# H21R2.net
KiCad netlist of a schematic drawn in EAGLE
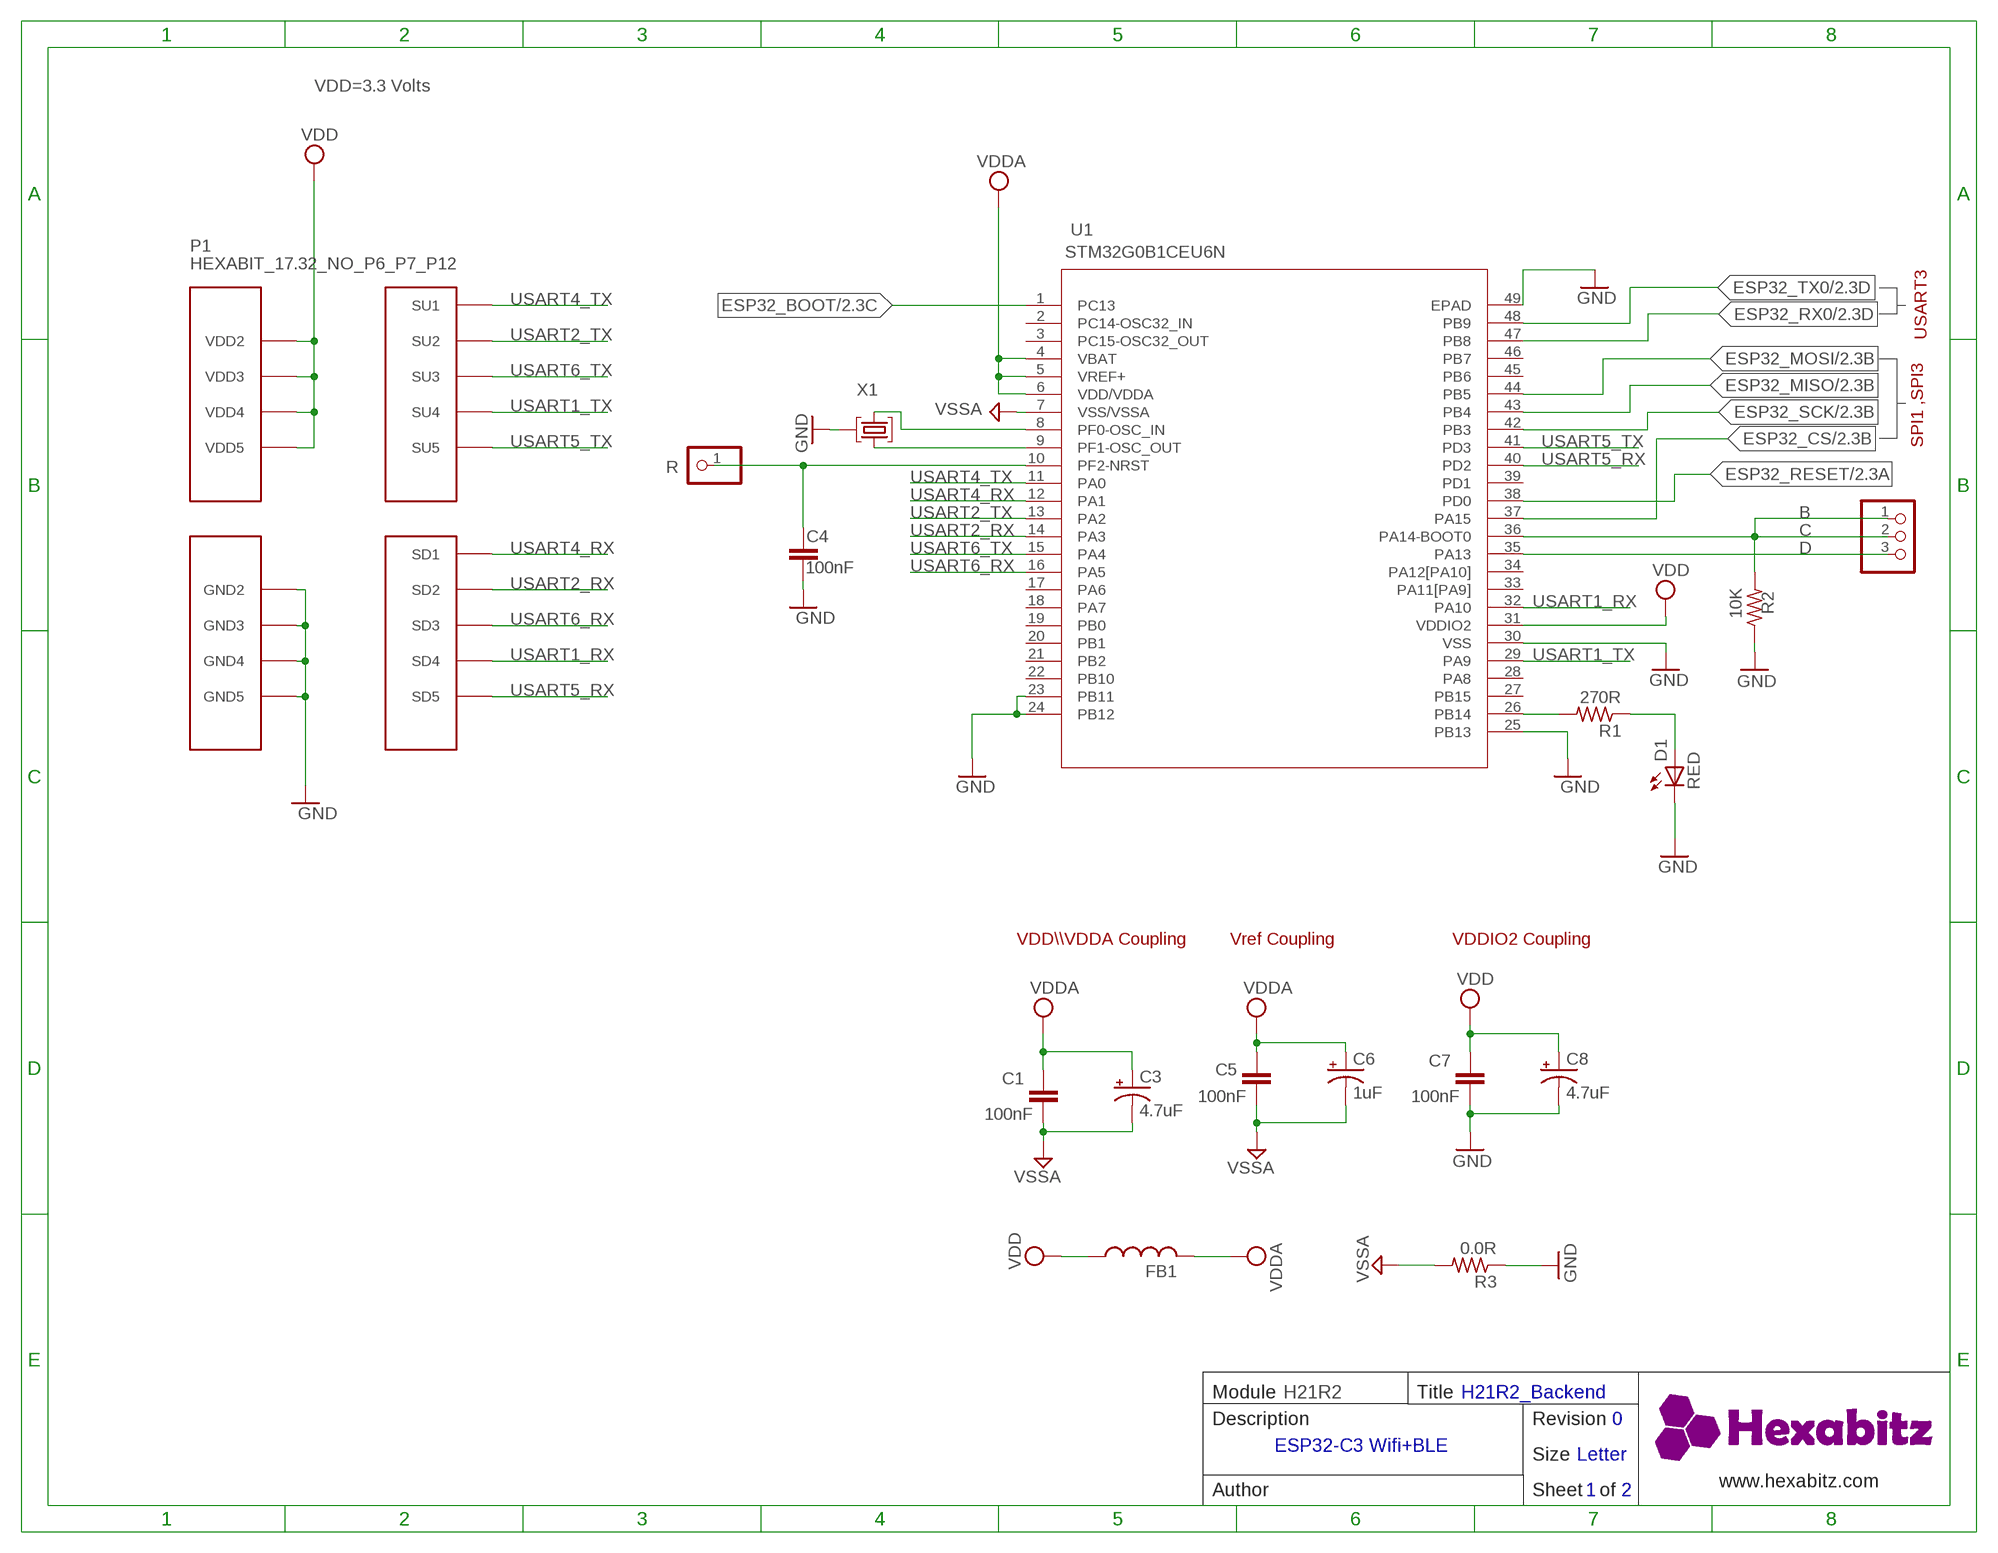
[diagram p0: schematic, sheet 1]
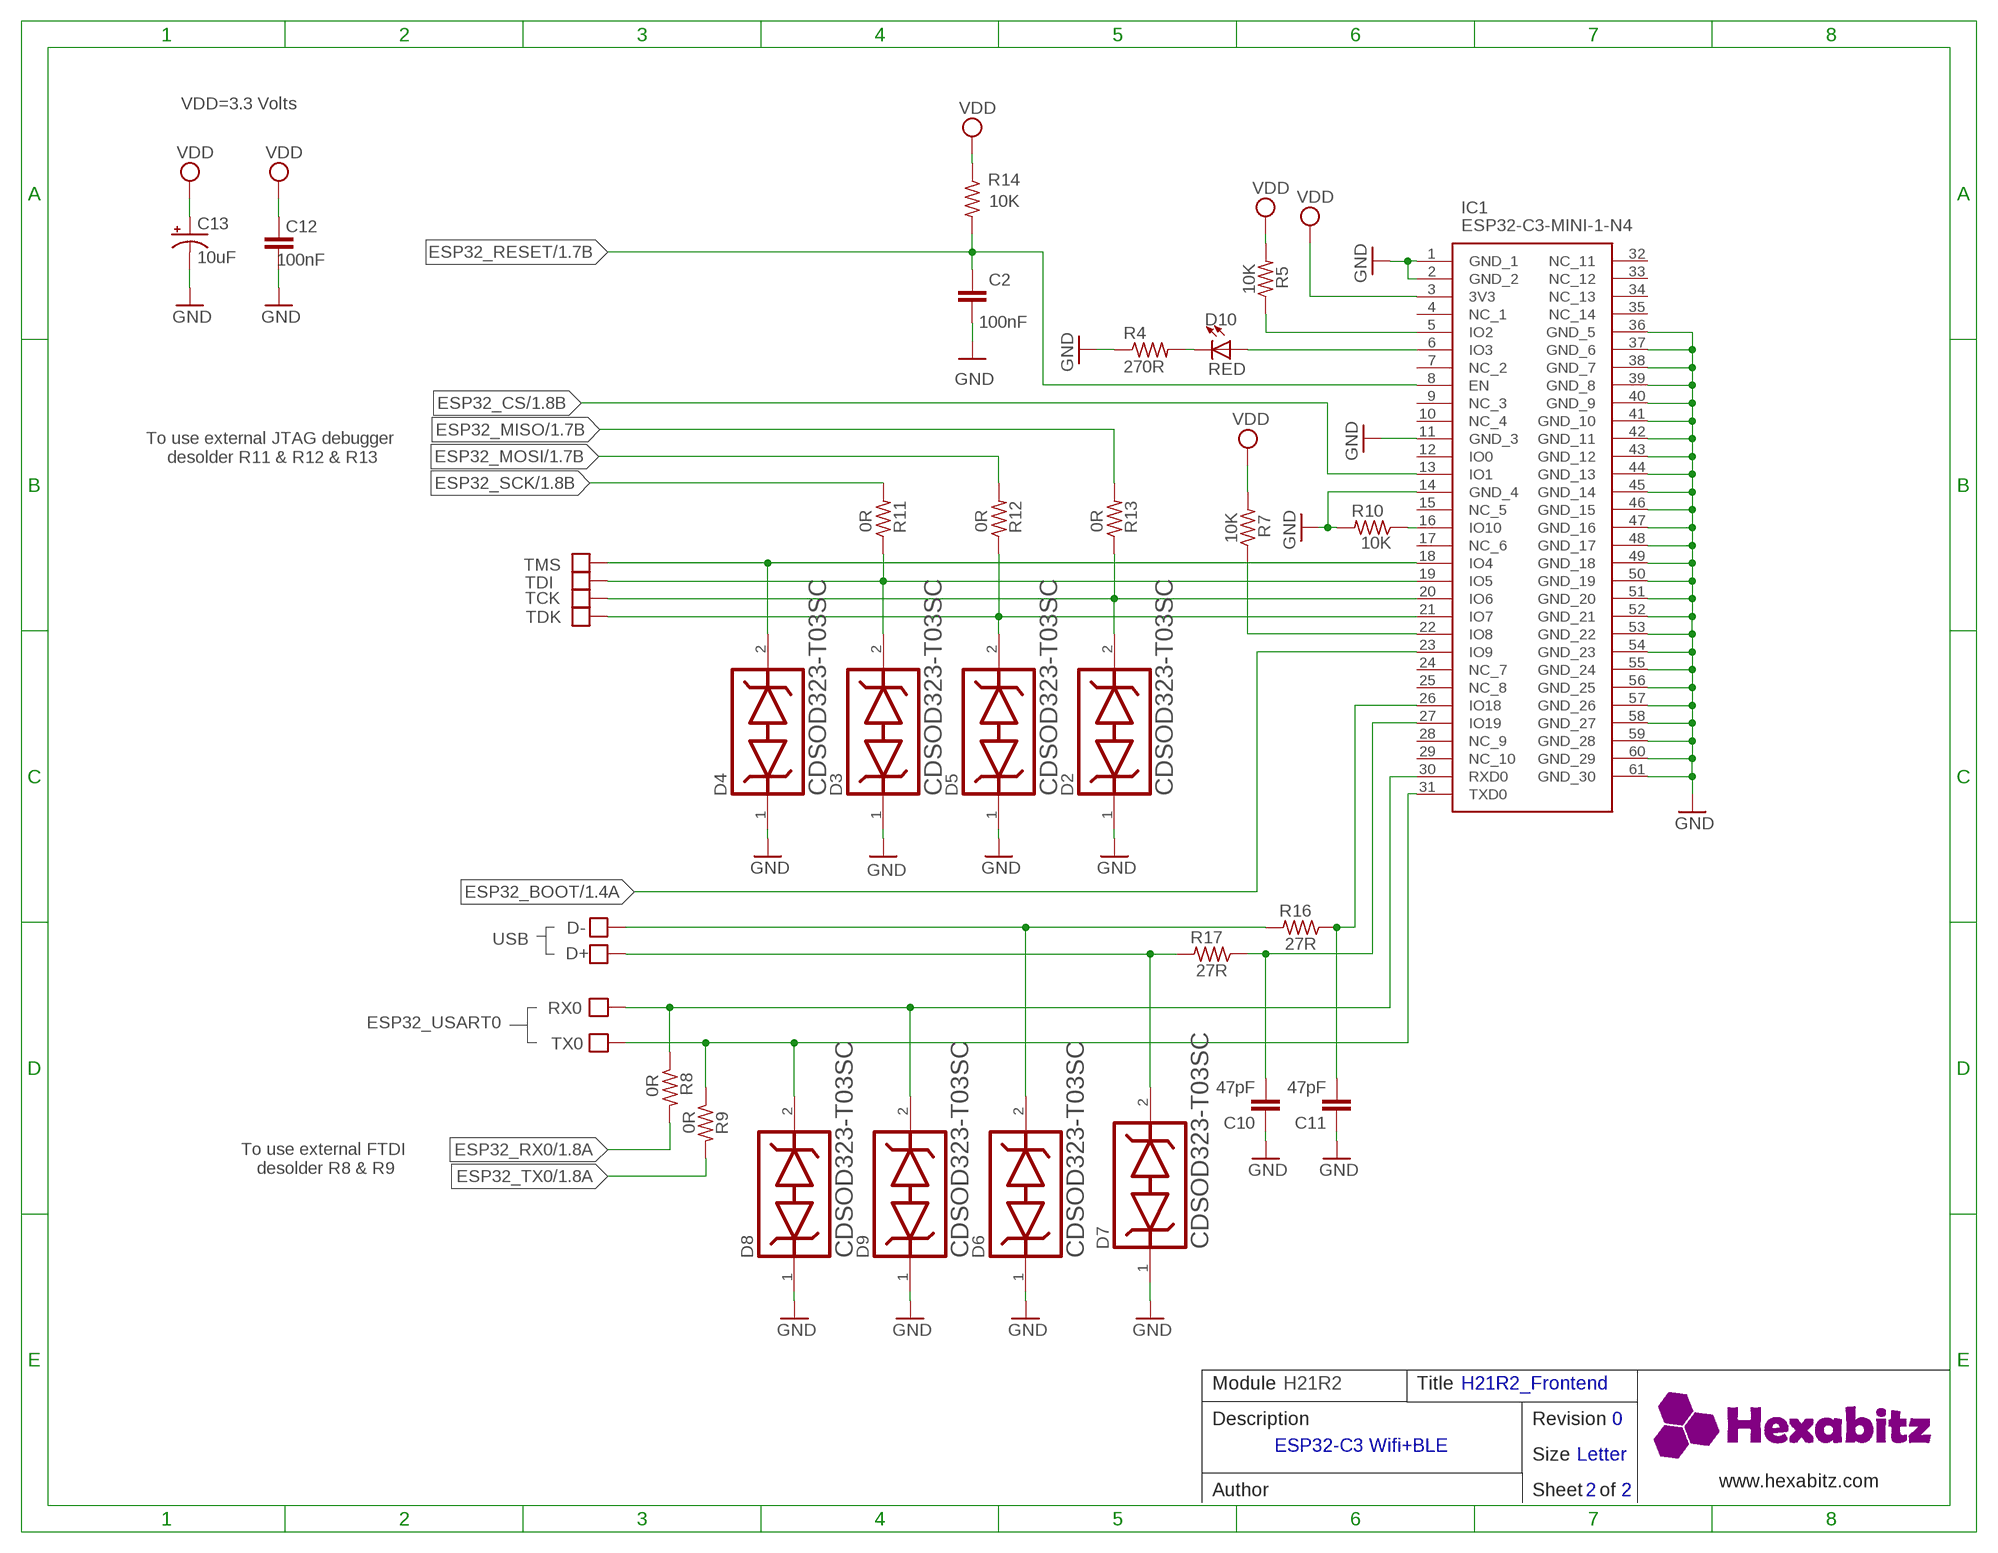
[diagram p1: schematic, sheet 2]

(export (version "E")
  (design (tool "Eeschema 10.0.6"))
  (components
    (comp (ref "C1")
      (value "100nF")
      (footprint "eagle-import:C-0603")
      (fields
        (field (name "CAPACITANCE") "100nF")
        (field (name "MFN") "AVX CORPORATION")
        (field (name "MPN") "'0603YC104K4T2A")
        (field (name "OCTOPART_URL") "'https://octopart.com/0603yc104k4t2a-avx+interconnect+%2F+elco-8120651")
        (field (name "TOLERANCE") "10%")
        (field (name "VOLTAGE_RATING") "16.0 V")
      )
      (libsource (lib "eagle-import") (part "C-0603"))
    )
    (comp (ref "C3")
      (value "4.7uF")
      (footprint "eagle-import:C-0805-POL")
      (fields
        (field (name "CAPACITANCE") "4.7uF")
        (field (name "MFN") "'Panasonic")
        (field (name "MPN") "'10TPU4R7MSI")
        (field (name "OCTOPART_URL") "https://octopart.com/10tpu4r7msi-panasonic-29487748?r=sp")
        (field (name "TOLERANCE") "20%")
        (field (name "VOLTAGE_RATING") "10.0 V")
      )
      (libsource (lib "eagle-import") (part "C-0805-POL"))
    )
    (comp (ref "C4")
      (value "100nF")
      (footprint "eagle-import:C-0603")
      (fields
        (field (name "CAPACITANCE") "100nF")
        (field (name "MFN") "AVX CORPORATION")
        (field (name "MPN") "0603YC104K4T2A")
        (field (name "OCTOPART_URL") "'https://octopart.com/0603yc104k4t2a-avx+interconnect+%2F+elco-8120651")
        (field (name "TOLERANCE") "10%")
        (field (name "VOLTAGE_RATING") "16.0 V")
      )
      (libsource (lib "eagle-import") (part "C-0603"))
    )
    (comp (ref "C5")
      (value "100nF")
      (footprint "eagle-import:C-0603")
      (fields
        (field (name "CAPACITANCE") "100nF")
        (field (name "MFN") "AVX CORPORATION")
        (field (name "MPN") "'0603YC104K4T2A")
        (field (name "OCTOPART_URL") "'https://octopart.com/0603yc104k4t2a-avx+interconnect+%2F+elco-8120651")
        (field (name "TOLERANCE") "10%")
        (field (name "VOLTAGE_RATING") "16.0 V")
      )
      (libsource (lib "eagle-import") (part "C-0603"))
    )
    (comp (ref "C6")
      (value "1uF")
      (footprint "eagle-import:C-0805-POL")
      (fields
        (field (name "CAPACITANCE") "4.7uF")
        (field (name "MFN") "'YAGEO [VA]")
        (field (name "MPN") "'CC0805KKX7R7BB105")
        (field (name "OCTOPART_URL") "'https://octopart.com/cc0805kkx7r7bb105-yageo-8376555?r=sp")
        (field (name "TOLERANCE") "20%")
        (field (name "VOLTAGE_RATING") "10.0 V")
      )
      (libsource (lib "eagle-import") (part "C-0805-POL"))
    )
    (comp (ref "C7")
      (value "100nF")
      (footprint "eagle-import:C-0603")
      (fields
        (field (name "CAPACITANCE") "100nF")
        (field (name "MFN") "AVX CORPORATION")
        (field (name "MPN") "'0603YC104K4T2A")
        (field (name "OCTOPART_URL") "'https://octopart.com/0603yc104k4t2a-avx+interconnect+%2F+elco-8120651")
        (field (name "TOLERANCE") "10%")
        (field (name "VOLTAGE_RATING") "16.0 V")
      )
      (libsource (lib "eagle-import") (part "C-0603"))
    )
    (comp (ref "C8")
      (value "4.7uF")
      (footprint "eagle-import:C-0805-POL")
      (fields
        (field (name "CAPACITANCE") "1.00uF")
        (field (name "MFN") "'Panasonic")
        (field (name "MPN") "'10TPU4R7MSI")
        (field (name "OCTOPART_URL") "https://octopart.com/10tpu4r7msi-panasonic-29487748?r=sp")
        (field (name "TOLERANCE") "10%")
        (field (name "VOLTAGE_RATING") "16.0 V")
      )
      (libsource (lib "eagle-import") (part "C-0805-POL"))
    )
    (comp (ref "D1")
      (value "RED")
      (footprint "eagle-import:VLMS1300-GS08")
      (fields (field (name "MPN") "VLMS1300-GS08"))
      (libsource (lib "eagle-import") (part "VLMS1300-GS08"))
    )
    (comp (ref "FB1")
      (value "FB-TDK_MMZ1608Y300B")
      (footprint "eagle-import:FB-TDK_MMZ1608Y300B")
      (fields
        (field (name "MFN") "TDK ")
        (field (name "MPN") "MMZ1608Y300BTA00")
        (field (name "OCTOPART_URL") "https://octopart.com/mmz1608y300bta00-tdk-7906990?r=sp")
      )
      (libsource (lib "eagle-import") (part "FB-TDK_MMZ1608Y300B"))
    )
    (comp (ref "JP1")
      (value "PINHD-1X3")
      (footprint "eagle-import:1X03")
      (libsource (lib "eagle-import") (part "PINHD-1X3"))
    )
    (comp (ref "P1")
      (value "HEXABIT_17.32_NO_P6_P7_P12")
      (footprint "eagle-import:HEXABIT_17.32_NO_P6_P7_P12")
      (libsource (lib "eagle-import") (part "HEXABIT_?_NO_P6_P7_P1217.32"))
    )
    (comp (ref "R")
      (value "PINHD-1X1")
      (footprint "eagle-import:1X01")
      (fields (field (name "MPN") "87227-1"))
      (libsource (lib "eagle-import") (part "PINHD-1X1"))
    )
    (comp (ref "R1")
      (value "270R")
      (footprint "eagle-import:R-0603")
      (fields
        (field (name "MFN") "'Panasonic")
        (field (name "MPN") "'ERJ-3GEYJ271V")
        (field (name "OCTOPART_URL") "https://octopart.com/erj-3geyj271v-panasonic-55560546?r=sp")
        (field (name "RESISTANCE") "270R")
      )
      (libsource (lib "eagle-import") (part "R-0603"))
    )
    (comp (ref "R2")
      (value "10K")
      (footprint "eagle-import:R-0603")
      (fields
        (field (name "MFN") "Vishay")
        (field (name "MPN") "'060300J0103T5E")
        (field (name "OCTOPART_URL") "https://octopart.com/search?q=060300J0103T5E&currency=USD&specs=0")
        (field (name "RESISTANCE") "10K")
      )
      (libsource (lib "eagle-import") (part "R-0603"))
    )
    (comp (ref "R3")
      (value "0.0R")
      (footprint "eagle-import:R-0603")
      (fields
        (field (name "MFN") "YAGEO [VR]")
        (field (name "MPN") "RC0603JR-070RL")
        (field (name "OCTOPART_URL") "https://octopart.com/rc0603jr-070rl-yageo-1241539?r=sp")
        (field (name "RESISTANCE") "0R")
      )
      (libsource (lib "eagle-import") (part "R-0603"))
    )
    (comp (ref "U1")
      (value "STM32G0B1CEU6N")
      (footprint "eagle-import:HEXABITZ_ICS_QFN_B1CEU6_STM-L")
      (libsource (lib "eagle-import") (part "STM32G0B1CEU6N"))
    )
    (comp (ref "X1")
      (value "8MHZ")
      (footprint "eagle-import:XTALL_CSTCE8M00G52")
      (fields
        (field (name "MPN") "CSTCE8M00G52Z-R0")
        (field (name "MPN_1") "CSTNE8M00G550000R0")
        (field (name "OCTOPART_URL") "https://octopart.com/cstne8m00g550000r0-murata-91406934?r=sp")
      )
      (libsource (lib "eagle-import") (part "XTALL_CSTCE8M00G52"))
    )
    (comp (ref "C2")
      (value "100nF")
      (footprint "eagle-import:C-0603")
      (fields
        (field (name "CAPACITANCE") "100nF")
        (field (name "MFN") "AVX CORPORATION")
        (field (name "MPN") "'0603YC104K4T2A")
        (field (name "OCTOPART_URL") "'https://octopart.com/0603yc104k4t2a-avx+interconnect+%2F+elco-8120651")
        (field (name "TOLERANCE") "10%")
        (field (name "VOLTAGE_RATING") "16.0 V")
      )
      (libsource (lib "eagle-import") (part "C-0603"))
    )
    (comp (ref "C10")
      (value "47pF")
      (footprint "eagle-import:C-0603")
      (fields
        (field (name "CAPACITANCE") "100nF")
        (field (name "MFN") "AVX CORPORATION")
        (field (name "MPN") "'0603YC104K4T2A")
        (field (name "OCTOPART_URL") "'https://octopart.com/0603yc104k4t2a-avx+interconnect+%2F+elco-8120651")
        (field (name "TOLERANCE") "10%")
        (field (name "VOLTAGE_RATING") "16.0 V")
      )
      (libsource (lib "eagle-import") (part "C-0603"))
    )
    (comp (ref "C11")
      (value "47pF")
      (footprint "eagle-import:C-0603")
      (fields
        (field (name "CAPACITANCE") "100nF")
        (field (name "MFN") "AVX CORPORATION")
        (field (name "MPN") "'0603YC104K4T2A")
        (field (name "OCTOPART_URL") "'https://octopart.com/0603yc104k4t2a-avx+interconnect+%2F+elco-8120651")
        (field (name "TOLERANCE") "10%")
        (field (name "VOLTAGE_RATING") "16.0 V")
      )
      (libsource (lib "eagle-import") (part "C-0603"))
    )
    (comp (ref "C12")
      (value "100nF")
      (footprint "eagle-import:C-0603")
      (fields
        (field (name "CAPACITANCE") "100nF")
        (field (name "MFN") "AVX CORPORATION")
        (field (name "MPN") "'0603YC104K4T2A")
        (field (name "OCTOPART_URL") "'https://octopart.com/0603yc104k4t2a-avx+interconnect+%2F+elco-8120651")
        (field (name "TOLERANCE") "10%")
        (field (name "VOLTAGE_RATING") "16.0 V")
      )
      (libsource (lib "eagle-import") (part "C-0603"))
    )
    (comp (ref "C13")
      (value "10uF")
      (footprint "eagle-import:C-1210-POL")
      (libsource (lib "eagle-import") (part "C-1210-POL"))
    )
    (comp (ref "D+")
      (value "PAD4")
      (footprint "eagle-import:PAD4")
      (libsource (lib "eagle-import") (part "PAD4"))
    )
    (comp (ref "D-")
      (value "PAD4")
      (footprint "eagle-import:PAD4")
      (libsource (lib "eagle-import") (part "PAD4"))
    )
    (comp (ref "D2")
      (value "BOURNS_CDSOD323-T03SCBOURNS_CDSOD323-T03SC_0_0")
      (footprint "eagle-import:BOURNS_CDSOD323-T03SC_0")
      (fields (field (name "MPN") "CDSOD323-T03SC"))
      (libsource (lib "eagle-import") (part "BOURNS_CDSOD323-T03SCBOURNS_CDSOD323-T03SC_0_0"))
    )
    (comp (ref "D3")
      (value "BOURNS_CDSOD323-T03SCBOURNS_CDSOD323-T03SC_0_0")
      (footprint "eagle-import:BOURNS_CDSOD323-T03SC_0")
      (fields (field (name "MPN") "CDSOD323-T03SC"))
      (libsource (lib "eagle-import") (part "BOURNS_CDSOD323-T03SCBOURNS_CDSOD323-T03SC_0_0"))
    )
    (comp (ref "D4")
      (value "BOURNS_CDSOD323-T03SCBOURNS_CDSOD323-T03SC_0_0")
      (footprint "eagle-import:BOURNS_CDSOD323-T03SC_0")
      (fields (field (name "MPN") "CDSOD323-T03SC"))
      (libsource (lib "eagle-import") (part "BOURNS_CDSOD323-T03SCBOURNS_CDSOD323-T03SC_0_0"))
    )
    (comp (ref "D5")
      (value "BOURNS_CDSOD323-T03SCBOURNS_CDSOD323-T03SC_0_0")
      (footprint "eagle-import:BOURNS_CDSOD323-T03SC_0")
      (fields (field (name "MPN") "CDSOD323-T03SC"))
      (libsource (lib "eagle-import") (part "BOURNS_CDSOD323-T03SCBOURNS_CDSOD323-T03SC_0_0"))
    )
    (comp (ref "D6")
      (value "BOURNS_CDSOD323-T03SCBOURNS_CDSOD323-T03SC_0_0")
      (footprint "eagle-import:BOURNS_CDSOD323-T03SC_0")
      (fields (field (name "MPN") "CDSOD323-T03SC"))
      (libsource (lib "eagle-import") (part "BOURNS_CDSOD323-T03SCBOURNS_CDSOD323-T03SC_0_0"))
    )
    (comp (ref "D7")
      (value "BOURNS_CDSOD323-T03SCBOURNS_CDSOD323-T03SC_0_0")
      (footprint "eagle-import:BOURNS_CDSOD323-T03SC_0")
      (fields (field (name "MPN") "CDSOD323-T03SC"))
      (libsource (lib "eagle-import") (part "BOURNS_CDSOD323-T03SCBOURNS_CDSOD323-T03SC_0_0"))
    )
    (comp (ref "D8")
      (value "BOURNS_CDSOD323-T03SCBOURNS_CDSOD323-T03SC_0_0")
      (footprint "eagle-import:BOURNS_CDSOD323-T03SC_0")
      (fields (field (name "MPN") "CDSOD323-T03SC"))
      (libsource (lib "eagle-import") (part "BOURNS_CDSOD323-T03SCBOURNS_CDSOD323-T03SC_0_0"))
    )
    (comp (ref "D9")
      (value "BOURNS_CDSOD323-T03SCBOURNS_CDSOD323-T03SC_0_0")
      (footprint "eagle-import:BOURNS_CDSOD323-T03SC_0")
      (fields (field (name "MPN") "CDSOD323-T03SC"))
      (libsource (lib "eagle-import") (part "BOURNS_CDSOD323-T03SCBOURNS_CDSOD323-T03SC_0_0"))
    )
    (comp (ref "D10")
      (value "RED")
      (footprint "eagle-import:VLMS1300-GS08")
      (fields (field (name "MPN") "VLMS1300-GS08"))
      (libsource (lib "eagle-import") (part "VLMS1300-GS08"))
    )
    (comp (ref "IC1")
      (value "ESP32-C3-MINI-1-N4")
      (footprint "eagle-import:ESP32C3MINI1N4")
      (fields (field (name "MOUSER_PART_NUMBER") "356-ESP32-C3-MINI1N4"))
      (libsource (lib "eagle-import") (part "ESP32-C3-MINI-1-N4"))
    )
    (comp (ref "R4")
      (value "270R")
      (footprint "eagle-import:R-0603")
      (fields
        (field (name "MFN") "'Panasonic")
        (field (name "MPN") "'ERJ-3GEYJ271V")
        (field (name "OCTOPART_URL") "https://octopart.com/erj-3geyj271v-panasonic-55560546?r=sp")
        (field (name "RESISTANCE") "270R")
      )
      (libsource (lib "eagle-import") (part "R-0603"))
    )
    (comp (ref "R5")
      (value "10K")
      (footprint "eagle-import:R-0603")
      (fields
        (field (name "MFN") "YAGEO [VR]")
        (field (name "MPN") "RC0603JR-070RL")
        (field (name "OCTOPART_URL") "https://octopart.com/rc0603jr-070rl-yageo-1241539?r=sp")
        (field (name "RESISTANCE") "0R")
      )
      (libsource (lib "eagle-import") (part "R-0603"))
    )
    (comp (ref "R7")
      (value "10K")
      (footprint "eagle-import:R-0603")
      (fields
        (field (name "MFN") "YAGEO [VR]")
        (field (name "MPN") "RC0603JR-070RL")
        (field (name "OCTOPART_URL") "https://octopart.com/rc0603jr-070rl-yageo-1241539?r=sp")
        (field (name "RESISTANCE") "0R")
      )
      (libsource (lib "eagle-import") (part "R-0603"))
    )
    (comp (ref "R8")
      (value "0R")
      (footprint "eagle-import:R-0603")
      (fields
        (field (name "MFN") "YAGEO [VR]")
        (field (name "MPN") "RC0603JR-070RL")
        (field (name "OCTOPART_URL") "https://octopart.com/rc0603jr-070rl-yageo-1241539?r=sp")
        (field (name "RESISTANCE") "0R")
      )
      (libsource (lib "eagle-import") (part "R-0603"))
    )
    (comp (ref "R9")
      (value "0R")
      (footprint "eagle-import:R-0603")
      (fields
        (field (name "MFN") "YAGEO [VR]")
        (field (name "MPN") "RC0603JR-070RL")
        (field (name "OCTOPART_URL") "https://octopart.com/rc0603jr-070rl-yageo-1241539?r=sp")
        (field (name "RESISTANCE") "0R")
      )
      (libsource (lib "eagle-import") (part "R-0603"))
    )
    (comp (ref "R10")
      (value "10K")
      (footprint "eagle-import:R-0603")
      (fields
        (field (name "MFN") "YAGEO [VR]")
        (field (name "MPN") "RC0603JR-070RL")
        (field (name "OCTOPART_URL") "https://octopart.com/rc0603jr-070rl-yageo-1241539?r=sp")
        (field (name "RESISTANCE") "0R")
      )
      (libsource (lib "eagle-import") (part "R-0603"))
    )
    (comp (ref "R11")
      (value "0R")
      (footprint "eagle-import:R-0402")
      (fields
        (field (name "MFN") "YAGEO [VR]")
        (field (name "MPN") "RC0603JR-070RL")
        (field (name "OCTOPART_URL") "https://octopart.com/rc0603jr-070rl-yageo-1241539?r=sp")
        (field (name "RESISTANCE") "0R")
      )
      (libsource (lib "eagle-import") (part "R-0402"))
    )
    (comp (ref "R12")
      (value "0R")
      (footprint "eagle-import:R-0402")
      (fields
        (field (name "MFN") "YAGEO [VR]")
        (field (name "MPN") "RC0603JR-070RL")
        (field (name "OCTOPART_URL") "https://octopart.com/rc0603jr-070rl-yageo-1241539?r=sp")
        (field (name "RESISTANCE") "0R")
      )
      (libsource (lib "eagle-import") (part "R-0402"))
    )
    (comp (ref "R13")
      (value "0R")
      (footprint "eagle-import:R-0402")
      (fields
        (field (name "MFN") "YAGEO [VR]")
        (field (name "MPN") "RC0603JR-070RL")
        (field (name "OCTOPART_URL") "https://octopart.com/rc0603jr-070rl-yageo-1241539?r=sp")
        (field (name "RESISTANCE") "0R")
      )
      (libsource (lib "eagle-import") (part "R-0402"))
    )
    (comp (ref "R14")
      (value "10K")
      (footprint "eagle-import:R-0603")
      (fields
        (field (name "MFN") "YAGEO [VR]")
        (field (name "MPN") "RC0603JR-070RL")
        (field (name "OCTOPART_URL") "https://octopart.com/rc0603jr-070rl-yageo-1241539?r=sp")
        (field (name "RESISTANCE") "0R")
      )
      (libsource (lib "eagle-import") (part "R-0603"))
    )
    (comp (ref "R16")
      (value "27R")
      (footprint "eagle-import:R-0603")
      (fields
        (field (name "MFN") "YAGEO [VR]")
        (field (name "MPN") "RC0603JR-070RL")
        (field (name "OCTOPART_URL") "https://octopart.com/rc0603jr-070rl-yageo-1241539?r=sp")
        (field (name "RESISTANCE") "0R")
      )
      (libsource (lib "eagle-import") (part "R-0603"))
    )
    (comp (ref "R17")
      (value "27R")
      (footprint "eagle-import:R-0603")
      (fields
        (field (name "MFN") "YAGEO [VR]")
        (field (name "MPN") "RC0603JR-070RL")
        (field (name "OCTOPART_URL") "https://octopart.com/rc0603jr-070rl-yageo-1241539?r=sp")
        (field (name "RESISTANCE") "0R")
      )
      (libsource (lib "eagle-import") (part "R-0603"))
    )
    (comp (ref "RX0")
      (value "PAD4")
      (footprint "eagle-import:PAD4")
      (libsource (lib "eagle-import") (part "PAD4"))
    )
    (comp (ref "TCK")
      (value "PAD4")
      (footprint "eagle-import:PAD4")
      (libsource (lib "eagle-import") (part "PAD4"))
    )
    (comp (ref "TDI")
      (value "PAD4")
      (footprint "eagle-import:PAD4")
      (libsource (lib "eagle-import") (part "PAD4"))
    )
    (comp (ref "TDK")
      (value "PAD4")
      (footprint "eagle-import:PAD4")
      (libsource (lib "eagle-import") (part "PAD4"))
    )
    (comp (ref "TMS")
      (value "PAD4")
      (footprint "eagle-import:PAD4")
      (libsource (lib "eagle-import") (part "PAD4"))
    )
    (comp (ref "TX0")
      (value "PAD4")
      (footprint "eagle-import:PAD4")
      (libsource (lib "eagle-import") (part "PAD4"))
    )
  )
  (nets
    (net (code "1") (name "C") (class "Default")
      (node (ref "JP1") (pin "1") (pinfunction "1_1") (pintype "passive"))
      (node (ref "JP1") (pin "2") (pinfunction "2_2") (pintype "passive"))
      (node (ref "R2") (pin "2") (pinfunction "2_2") (pintype "passive"))
      (node (ref "U1") (pin "36") (pinfunction "PA14-BOOT0_36") (pintype "bidirectional"))
    )
    (net (code "2") (name "D") (class "Default")
      (node (ref "JP1") (pin "3") (pinfunction "3_3") (pintype "passive"))
      (node (ref "U1") (pin "35") (pinfunction "PA13_35") (pintype "bidirectional"))
    )
    (net (code "3") (name "ESP32_BOOT") (class "Default")
      (node (ref "IC1") (pin "23") (pinfunction "IO9_23") (pintype "bidirectional"))
      (node (ref "U1") (pin "1") (pinfunction "PC13_1") (pintype "bidirectional"))
    )
    (net (code "4") (name "ESP32_CS") (class "Default")
      (node (ref "IC1") (pin "13") (pinfunction "IO1_13") (pintype "bidirectional"))
      (node (ref "U1") (pin "37") (pinfunction "PA15_37") (pintype "bidirectional"))
    )
    (net (code "5") (name "ESP32_MISO") (class "Default")
      (node (ref "R13") (pin "2") (pinfunction "2_2") (pintype "passive"))
      (node (ref "U1") (pin "43") (pinfunction "PB4_43") (pintype "bidirectional"))
    )
    (net (code "6") (name "ESP32_MOSI") (class "Default")
      (node (ref "R12") (pin "2") (pinfunction "2_2") (pintype "passive"))
      (node (ref "U1") (pin "44") (pinfunction "PB5_44") (pintype "bidirectional"))
    )
    (net (code "7") (name "ESP32_RESET") (class "Default")
      (node (ref "C2") (pin "2") (pinfunction "2_2") (pintype "passive"))
      (node (ref "IC1") (pin "8") (pinfunction "EN_8") (pintype "bidirectional"))
      (node (ref "R14") (pin "2") (pinfunction "2_2") (pintype "passive"))
      (node (ref "U1") (pin "38") (pinfunction "PD0_38") (pintype "bidirectional"))
    )
    (net (code "8") (name "ESP32_RX0") (class "Default")
      (node (ref "R8") (pin "2") (pinfunction "2_2") (pintype "passive"))
      (node (ref "U1") (pin "47") (pinfunction "PB8_47") (pintype "bidirectional"))
    )
    (net (code "9") (name "ESP32_SCK") (class "Default")
      (node (ref "R11") (pin "2") (pinfunction "2_2") (pintype "passive"))
      (node (ref "U1") (pin "42") (pinfunction "PB3_42") (pintype "bidirectional"))
    )
    (net (code "10") (name "ESP32_TX0") (class "Default")
      (node (ref "R9") (pin "2") (pinfunction "2_2") (pintype "passive"))
      (node (ref "U1") (pin "48") (pinfunction "PB9_48") (pintype "bidirectional"))
    )
    (net (code "11") (name "GND") (class "Default")
      (node (ref "C10") (pin "1") (pinfunction "1_1") (pintype "passive"))
      (node (ref "C11") (pin "1") (pinfunction "1_1") (pintype "passive"))
      (node (ref "C12") (pin "1") (pinfunction "1_1") (pintype "passive"))
      (node (ref "C13") (pin "2") (pinfunction "-_2") (pintype "passive"))
      (node (ref "C2") (pin "1") (pinfunction "1_1") (pintype "passive"))
      (node (ref "C4") (pin "1") (pinfunction "1_1") (pintype "passive"))
      (node (ref "C7") (pin "1") (pinfunction "1_1") (pintype "passive"))
      (node (ref "C8") (pin "2") (pinfunction "-_2") (pintype "passive"))
      (node (ref "D1") (pin "C") (pinfunction "C_C") (pintype "passive"))
      (node (ref "D2") (pin "1") (pinfunction "1_1") (pintype "bidirectional"))
      (node (ref "D3") (pin "1") (pinfunction "1_1") (pintype "bidirectional"))
      (node (ref "D4") (pin "1") (pinfunction "1_1") (pintype "bidirectional"))
      (node (ref "D5") (pin "1") (pinfunction "1_1") (pintype "bidirectional"))
      (node (ref "D6") (pin "1") (pinfunction "1_1") (pintype "bidirectional"))
      (node (ref "D7") (pin "1") (pinfunction "1_1") (pintype "bidirectional"))
      (node (ref "D8") (pin "1") (pinfunction "1_1") (pintype "bidirectional"))
      (node (ref "D9") (pin "1") (pinfunction "1_1") (pintype "bidirectional"))
      (node (ref "IC1") (pin "1") (pinfunction "GND_1_1") (pintype "bidirectional"))
      (node (ref "IC1") (pin "11") (pinfunction "GND_3_11") (pintype "bidirectional"))
      (node (ref "IC1") (pin "14") (pinfunction "GND_4_14") (pintype "bidirectional"))
      (node (ref "IC1") (pin "2") (pinfunction "GND_2_2") (pintype "bidirectional"))
      (node (ref "IC1") (pin "36") (pinfunction "GND_5_36") (pintype "bidirectional"))
      (node (ref "IC1") (pin "37") (pinfunction "GND_6_37") (pintype "bidirectional"))
      (node (ref "IC1") (pin "38") (pinfunction "GND_7_38") (pintype "bidirectional"))
      (node (ref "IC1") (pin "39") (pinfunction "GND_8_39") (pintype "bidirectional"))
      (node (ref "IC1") (pin "40") (pinfunction "GND_9_40") (pintype "bidirectional"))
      (node (ref "IC1") (pin "41") (pinfunction "GND_10_41") (pintype "bidirectional"))
      (node (ref "IC1") (pin "42") (pinfunction "GND_11_42") (pintype "bidirectional"))
      (node (ref "IC1") (pin "43") (pinfunction "GND_12_43") (pintype "bidirectional"))
      (node (ref "IC1") (pin "44") (pinfunction "GND_13_44") (pintype "bidirectional"))
      (node (ref "IC1") (pin "45") (pinfunction "GND_14_45") (pintype "bidirectional"))
      (node (ref "IC1") (pin "46") (pinfunction "GND_15_46") (pintype "bidirectional"))
      (node (ref "IC1") (pin "47") (pinfunction "GND_16_47") (pintype "bidirectional"))
      (node (ref "IC1") (pin "48") (pinfunction "GND_17_48") (pintype "bidirectional"))
      (node (ref "IC1") (pin "49") (pinfunction "GND_18_49") (pintype "bidirectional"))
      (node (ref "IC1") (pin "50") (pinfunction "GND_19_50") (pintype "bidirectional"))
      (node (ref "IC1") (pin "51") (pinfunction "GND_20_51") (pintype "bidirectional"))
      (node (ref "IC1") (pin "52") (pinfunction "GND_21_52") (pintype "bidirectional"))
      (node (ref "IC1") (pin "53") (pinfunction "GND_22_53") (pintype "bidirectional"))
      (node (ref "IC1") (pin "54") (pinfunction "GND_23_54") (pintype "bidirectional"))
      (node (ref "IC1") (pin "55") (pinfunction "GND_24_55") (pintype "bidirectional"))
      (node (ref "IC1") (pin "56") (pinfunction "GND_25_56") (pintype "bidirectional"))
      (node (ref "IC1") (pin "57") (pinfunction "GND_26_57") (pintype "bidirectional"))
      (node (ref "IC1") (pin "58") (pinfunction "GND_27_58") (pintype "bidirectional"))
      (node (ref "IC1") (pin "59") (pinfunction "GND_28_59") (pintype "bidirectional"))
      (node (ref "IC1") (pin "60") (pinfunction "GND_29_60") (pintype "bidirectional"))
      (node (ref "IC1") (pin "61") (pinfunction "GND_30_61") (pintype "bidirectional"))
      (node (ref "P1") (pin "PAD_PD10") (pinfunction "GND4_PAD_PD10") (pintype "power_in"))
      (node (ref "P1") (pin "PAD_PD11") (pinfunction "GND5_PAD_PD11") (pintype "power_in"))
      (node (ref "P1") (pin "PAD_PD8") (pinfunction "GND2_PAD_PD8") (pintype "power_in"))
      (node (ref "P1") (pin "PAD_PD9") (pinfunction "GND3_PAD_PD9") (pintype "power_in"))
      (node (ref "R10") (pin "2") (pinfunction "2_2") (pintype "passive"))
      (node (ref "R2") (pin "1") (pinfunction "1_1") (pintype "passive"))
      (node (ref "R3") (pin "1") (pinfunction "1_1") (pintype "passive"))
      (node (ref "R4") (pin "1") (pinfunction "1_1") (pintype "passive"))
      (node (ref "U1") (pin "23") (pinfunction "PB11_23") (pintype "bidirectional"))
      (node (ref "U1") (pin "24") (pinfunction "PB12_24") (pintype "bidirectional"))
      (node (ref "U1") (pin "25") (pinfunction "PB13_25") (pintype "bidirectional"))
      (node (ref "U1") (pin "30") (pinfunction "VSS_30") (pintype "passive"))
      (node (ref "U1") (pin "49") (pinfunction "EPAD_49") (pintype "passive"))
      (node (ref "X1") (pin "P$2") (pinfunction "2_P$2") (pintype "passive"))
    )
    (net (code "12") (name "Net-(D+-PadP$1)") (class "Default")
      (node (ref "D+") (pin "P$1") (pinfunction "P$1_P$1") (pintype "passive"))
      (node (ref "D7") (pin "2") (pinfunction "2_2") (pintype "bidirectional"))
      (node (ref "R17") (pin "2") (pinfunction "2_2") (pintype "passive"))
    )
    (net (code "13") (name "Net-(D--PadP$1)") (class "Default")
      (node (ref "D-") (pin "P$1") (pinfunction "P$1_P$1") (pintype "passive"))
      (node (ref "D6") (pin "2") (pinfunction "2_2") (pintype "bidirectional"))
      (node (ref "R16") (pin "2") (pinfunction "2_2") (pintype "passive"))
    )
    (net (code "14") (name "Net-(D1-PadA)") (class "Default")
      (node (ref "D1") (pin "A") (pinfunction "A_A") (pintype "passive"))
      (node (ref "R1") (pin "1") (pinfunction "1_1") (pintype "passive"))
    )
    (net (code "15") (name "Net-(D10-PadC)") (class "Default")
      (node (ref "D10") (pin "C") (pinfunction "C_C") (pintype "passive"))
      (node (ref "R4") (pin "2") (pinfunction "2_2") (pintype "passive"))
    )
    (net (code "16") (name "Net-(IC1-IO2)") (class "Default")
      (node (ref "IC1") (pin "5") (pinfunction "IO2_5") (pintype "bidirectional"))
      (node (ref "R5") (pin "1") (pinfunction "1_1") (pintype "passive"))
    )
    (net (code "17") (name "Net-(IC1-IO3)") (class "Default")
      (node (ref "D10") (pin "A") (pinfunction "A_A") (pintype "passive"))
      (node (ref "IC1") (pin "6") (pinfunction "IO3_6") (pintype "bidirectional"))
    )
    (net (code "18") (name "Net-(IC1-IO4)") (class "Default")
      (node (ref "D4") (pin "2") (pinfunction "2_2") (pintype "bidirectional"))
      (node (ref "IC1") (pin "18") (pinfunction "IO4_18") (pintype "bidirectional"))
      (node (ref "TMS") (pin "P$1") (pinfunction "P$1_P$1") (pintype "passive"))
    )
    (net (code "19") (name "Net-(IC1-IO5)") (class "Default")
      (node (ref "D3") (pin "2") (pinfunction "2_2") (pintype "bidirectional"))
      (node (ref "IC1") (pin "19") (pinfunction "IO5_19") (pintype "bidirectional"))
      (node (ref "R11") (pin "1") (pinfunction "1_1") (pintype "passive"))
      (node (ref "TDI") (pin "P$1") (pinfunction "P$1_P$1") (pintype "passive"))
    )
    (net (code "20") (name "Net-(IC1-IO6)") (class "Default")
      (node (ref "D2") (pin "2") (pinfunction "2_2") (pintype "bidirectional"))
      (node (ref "IC1") (pin "20") (pinfunction "IO6_20") (pintype "bidirectional"))
      (node (ref "R13") (pin "1") (pinfunction "1_1") (pintype "passive"))
      (node (ref "TCK") (pin "P$1") (pinfunction "P$1_P$1") (pintype "passive"))
    )
    (net (code "21") (name "Net-(IC1-IO7)") (class "Default")
      (node (ref "D5") (pin "2") (pinfunction "2_2") (pintype "bidirectional"))
      (node (ref "IC1") (pin "21") (pinfunction "IO7_21") (pintype "bidirectional"))
      (node (ref "R12") (pin "1") (pinfunction "1_1") (pintype "passive"))
      (node (ref "TDK") (pin "P$1") (pinfunction "P$1_P$1") (pintype "passive"))
    )
    (net (code "22") (name "Net-(IC1-IO8)") (class "Default")
      (node (ref "IC1") (pin "22") (pinfunction "IO8_22") (pintype "bidirectional"))
      (node (ref "R7") (pin "1") (pinfunction "1_1") (pintype "passive"))
    )
    (net (code "23") (name "Net-(IC1-IO10)") (class "Default")
      (node (ref "IC1") (pin "16") (pinfunction "IO10_16") (pintype "bidirectional"))
      (node (ref "R10") (pin "1") (pinfunction "1_1") (pintype "passive"))
    )
    (net (code "24") (name "Net-(IC1-IO18)") (class "Default")
      (node (ref "C11") (pin "2") (pinfunction "2_2") (pintype "passive"))
      (node (ref "IC1") (pin "26") (pinfunction "IO18_26") (pintype "bidirectional"))
      (node (ref "R16") (pin "1") (pinfunction "1_1") (pintype "passive"))
    )
    (net (code "25") (name "Net-(IC1-IO19)") (class "Default")
      (node (ref "C10") (pin "2") (pinfunction "2_2") (pintype "passive"))
      (node (ref "IC1") (pin "27") (pinfunction "IO19_27") (pintype "bidirectional"))
      (node (ref "R17") (pin "1") (pinfunction "1_1") (pintype "passive"))
    )
    (net (code "26") (name "Net-(IC1-RXD0)") (class "Default")
      (node (ref "D9") (pin "2") (pinfunction "2_2") (pintype "bidirectional"))
      (node (ref "IC1") (pin "30") (pinfunction "RXD0_30") (pintype "bidirectional"))
      (node (ref "R8") (pin "1") (pinfunction "1_1") (pintype "passive"))
      (node (ref "RX0") (pin "P$1") (pinfunction "P$1_P$1") (pintype "passive"))
    )
    (net (code "27") (name "Net-(IC1-TXD0)") (class "Default")
      (node (ref "D8") (pin "2") (pinfunction "2_2") (pintype "bidirectional"))
      (node (ref "IC1") (pin "31") (pinfunction "TXD0_31") (pintype "bidirectional"))
      (node (ref "R9") (pin "1") (pinfunction "1_1") (pintype "passive"))
      (node (ref "TX0") (pin "P$1") (pinfunction "P$1_P$1") (pintype "passive"))
    )
    (net (code "28") (name "Net-(U1-PB14)") (class "Default")
      (node (ref "R1") (pin "2") (pinfunction "2_2") (pintype "passive"))
      (node (ref "U1") (pin "26") (pinfunction "PB14_26") (pintype "bidirectional"))
    )
    (net (code "29") (name "Net-(U1-PF0-OSC_IN)") (class "Default")
      (node (ref "U1") (pin "8") (pinfunction "PF0-OSC_IN_8") (pintype "bidirectional"))
      (node (ref "X1") (pin "P$1") (pinfunction "1_P$1") (pintype "passive"))
    )
    (net (code "30") (name "Net-(U1-PF1-OSC_OUT)") (class "Default")
      (node (ref "U1") (pin "9") (pinfunction "PF1-OSC_OUT_9") (pintype "bidirectional"))
      (node (ref "X1") (pin "P$3") (pinfunction "3_P$3") (pintype "passive"))
    )
    (net (code "31") (name "Net-(U1-PF2-NRST)") (class "Default")
      (node (ref "C4") (pin "2") (pinfunction "2_2") (pintype "passive"))
      (node (ref "R") (pin "1") (pinfunction "1_1") (pintype "passive"))
      (node (ref "U1") (pin "10") (pinfunction "PF2-NRST_10") (pintype "bidirectional"))
    )
    (net (code "32") (name "USART1_RX") (class "Default")
      (node (ref "P1") (pin "PAD_PD4") (pinfunction "SD4_PAD_PD4") (pintype "bidirectional"))
      (node (ref "U1") (pin "32") (pinfunction "PA10_32") (pintype "bidirectional"))
    )
    (net (code "33") (name "USART1_TX") (class "Default")
      (node (ref "P1") (pin "PAD_PU4") (pinfunction "SU4_PAD_PU4") (pintype "bidirectional"))
      (node (ref "U1") (pin "29") (pinfunction "PA9_29") (pintype "bidirectional"))
    )
    (net (code "34") (name "USART2_RX") (class "Default")
      (node (ref "P1") (pin "PAD_PD2") (pinfunction "SD2_PAD_PD2") (pintype "bidirectional"))
      (node (ref "U1") (pin "14") (pinfunction "PA3_14") (pintype "bidirectional"))
    )
    (net (code "35") (name "USART2_TX") (class "Default")
      (node (ref "P1") (pin "PAD_PU2") (pinfunction "SU2_PAD_PU2") (pintype "bidirectional"))
      (node (ref "U1") (pin "13") (pinfunction "PA2_13") (pintype "bidirectional"))
    )
    (net (code "36") (name "USART4_RX") (class "Default")
      (node (ref "P1") (pin "PAD_PD1") (pinfunction "SD1_PAD_PD1") (pintype "bidirectional"))
      (node (ref "U1") (pin "12") (pinfunction "PA1_12") (pintype "bidirectional"))
    )
    (net (code "37") (name "USART4_TX") (class "Default")
      (node (ref "P1") (pin "PAD_PU1") (pinfunction "SU1_PAD_PU1") (pintype "bidirectional"))
      (node (ref "U1") (pin "11") (pinfunction "PA0_11") (pintype "bidirectional"))
    )
    (net (code "38") (name "USART5_RX") (class "Default")
      (node (ref "P1") (pin "PAD_PD5") (pinfunction "SD5_PAD_PD5") (pintype "bidirectional"))
      (node (ref "U1") (pin "40") (pinfunction "PD2_40") (pintype "bidirectional"))
    )
    (net (code "39") (name "USART5_TX") (class "Default")
      (node (ref "P1") (pin "PAD_PU5") (pinfunction "SU5_PAD_PU5") (pintype "bidirectional"))
      (node (ref "U1") (pin "41") (pinfunction "PD3_41") (pintype "bidirectional"))
    )
    (net (code "40") (name "USART6_RX") (class "Default")
      (node (ref "P1") (pin "PAD_PD3") (pinfunction "SD3_PAD_PD3") (pintype "bidirectional"))
      (node (ref "U1") (pin "16") (pinfunction "PA5_16") (pintype "bidirectional"))
    )
    (net (code "41") (name "USART6_TX") (class "Default")
      (node (ref "P1") (pin "PAD_PU3") (pinfunction "SU3_PAD_PU3") (pintype "bidirectional"))
      (node (ref "U1") (pin "15") (pinfunction "PA4_15") (pintype "bidirectional"))
    )
    (net (code "42") (name "VDD") (class "Default")
      (node (ref "C12") (pin "2") (pinfunction "2_2") (pintype "passive"))
      (node (ref "C13") (pin "1") (pinfunction "+_1") (pintype "passive"))
      (node (ref "C7") (pin "2") (pinfunction "2_2") (pintype "passive"))
      (node (ref "C8") (pin "1") (pinfunction "+_1") (pintype "passive"))
      (node (ref "FB1") (pin "1") (pinfunction "1_1") (pintype "passive"))
      (node (ref "IC1") (pin "3") (pinfunction "3V3_3") (pintype "bidirectional"))
      (node (ref "P1") (pin "PAD_PU10") (pinfunction "VDD4_PAD_PU10") (pintype "power_in"))
      (node (ref "P1") (pin "PAD_PU11") (pinfunction "VDD5_PAD_PU11") (pintype "power_in"))
      (node (ref "P1") (pin "PAD_PU8") (pinfunction "VDD2_PAD_PU8") (pintype "power_in"))
      (node (ref "P1") (pin "PAD_PU9") (pinfunction "VDD3_PAD_PU9") (pintype "power_in"))
      (node (ref "R14") (pin "1") (pinfunction "1_1") (pintype "passive"))
      (node (ref "R5") (pin "2") (pinfunction "2_2") (pintype "passive"))
      (node (ref "R7") (pin "2") (pinfunction "2_2") (pintype "passive"))
      (node (ref "U1") (pin "31") (pinfunction "VDDIO2_31") (pintype "power_in"))
    )
    (net (code "43") (name "VDDA") (class "Default")
      (node (ref "C1") (pin "2") (pinfunction "2_2") (pintype "passive"))
      (node (ref "C3") (pin "1") (pinfunction "+_1") (pintype "passive"))
      (node (ref "C5") (pin "2") (pinfunction "2_2") (pintype "passive"))
      (node (ref "C6") (pin "1") (pinfunction "+_1") (pintype "passive"))
      (node (ref "FB1") (pin "2") (pinfunction "2_2") (pintype "passive"))
      (node (ref "U1") (pin "4") (pinfunction "VBAT_4") (pintype "power_in"))
      (node (ref "U1") (pin "5") (pinfunction "VREF+_5") (pintype "power_in"))
      (node (ref "U1") (pin "6") (pinfunction "VDD/VDDA_6") (pintype "power_in"))
    )
    (net (code "44") (name "VSSA") (class "Default")
      (node (ref "C1") (pin "1") (pinfunction "1_1") (pintype "passive"))
      (node (ref "C3") (pin "2") (pinfunction "-_2") (pintype "passive"))
      (node (ref "C5") (pin "1") (pinfunction "1_1") (pintype "passive"))
      (node (ref "C6") (pin "2") (pinfunction "-_2") (pintype "passive"))
      (node (ref "R3") (pin "2") (pinfunction "2_2") (pintype "passive"))
      (node (ref "U1") (pin "7") (pinfunction "VSS/VSSA_7") (pintype "passive"))
    )
    (net (code "45") (name "unconnected-(IC1-IO0-Pad12)") (class "Default")
      (node (ref "IC1") (pin "12") (pinfunction "IO0_12") (pintype "bidirectional"))
    )
    (net (code "46") (name "unconnected-(IC1-NC_1-Pad4)") (class "Default")
      (node (ref "IC1") (pin "4") (pinfunction "NC_1_4") (pintype "bidirectional"))
    )
    (net (code "47") (name "unconnected-(IC1-NC_2-Pad7)") (class "Default")
      (node (ref "IC1") (pin "7") (pinfunction "NC_2_7") (pintype "bidirectional"))
    )
    (net (code "48") (name "unconnected-(IC1-NC_3-Pad9)") (class "Default")
      (node (ref "IC1") (pin "9") (pinfunction "NC_3_9") (pintype "bidirectional"))
    )
    (net (code "49") (name "unconnected-(IC1-NC_4-Pad10)") (class "Default")
      (node (ref "IC1") (pin "10") (pinfunction "NC_4_10") (pintype "bidirectional"))
    )
    (net (code "50") (name "unconnected-(IC1-NC_5-Pad15)") (class "Default")
      (node (ref "IC1") (pin "15") (pinfunction "NC_5_15") (pintype "bidirectional"))
    )
    (net (code "51") (name "unconnected-(IC1-NC_6-Pad17)") (class "Default")
      (node (ref "IC1") (pin "17") (pinfunction "NC_6_17") (pintype "bidirectional"))
    )
    (net (code "52") (name "unconnected-(IC1-NC_7-Pad24)") (class "Default")
      (node (ref "IC1") (pin "24") (pinfunction "NC_7_24") (pintype "bidirectional"))
    )
    (net (code "53") (name "unconnected-(IC1-NC_8-Pad25)") (class "Default")
      (node (ref "IC1") (pin "25") (pinfunction "NC_8_25") (pintype "bidirectional"))
    )
    (net (code "54") (name "unconnected-(IC1-NC_9-Pad28)") (class "Default")
      (node (ref "IC1") (pin "28") (pinfunction "NC_9_28") (pintype "bidirectional"))
    )
    (net (code "55") (name "unconnected-(IC1-NC_10-Pad29)") (class "Default")
      (node (ref "IC1") (pin "29") (pinfunction "NC_10_29") (pintype "bidirectional"))
    )
    (net (code "56") (name "unconnected-(IC1-NC_11-Pad32)") (class "Default")
      (node (ref "IC1") (pin "32") (pinfunction "NC_11_32") (pintype "bidirectional"))
    )
    (net (code "57") (name "unconnected-(IC1-NC_12-Pad33)") (class "Default")
      (node (ref "IC1") (pin "33") (pinfunction "NC_12_33") (pintype "bidirectional"))
    )
    (net (code "58") (name "unconnected-(IC1-NC_13-Pad34)") (class "Default")
      (node (ref "IC1") (pin "34") (pinfunction "NC_13_34") (pintype "bidirectional"))
    )
    (net (code "59") (name "unconnected-(IC1-NC_14-Pad35)") (class "Default")
      (node (ref "IC1") (pin "35") (pinfunction "NC_14_35") (pintype "bidirectional"))
    )
    (net (code "60") (name "unconnected-(U1-PA6-Pad17)") (class "Default")
      (node (ref "U1") (pin "17") (pinfunction "PA6_17") (pintype "bidirectional"))
    )
    (net (code "61") (name "unconnected-(U1-PA7-Pad18)") (class "Default")
      (node (ref "U1") (pin "18") (pinfunction "PA7_18") (pintype "bidirectional"))
    )
    (net (code "62") (name "unconnected-(U1-PA8-Pad28)") (class "Default")
      (node (ref "U1") (pin "28") (pinfunction "PA8_28") (pintype "bidirectional"))
    )
    (net (code "63") (name "unconnected-(U1-PA11[PA9]-Pad33)") (class "Default")
      (node (ref "U1") (pin "33") (pinfunction "PA11[PA9]_33") (pintype "bidirectional"))
    )
    (net (code "64") (name "unconnected-(U1-PA12[PA10]-Pad34)") (class "Default")
      (node (ref "U1") (pin "34") (pinfunction "PA12[PA10]_34") (pintype "bidirectional"))
    )
    (net (code "65") (name "unconnected-(U1-PB0-Pad19)") (class "Default")
      (node (ref "U1") (pin "19") (pinfunction "PB0_19") (pintype "bidirectional"))
    )
    (net (code "66") (name "unconnected-(U1-PB1-Pad20)") (class "Default")
      (node (ref "U1") (pin "20") (pinfunction "PB1_20") (pintype "bidirectional"))
    )
    (net (code "67") (name "unconnected-(U1-PB2-Pad21)") (class "Default")
      (node (ref "U1") (pin "21") (pinfunction "PB2_21") (pintype "bidirectional"))
    )
    (net (code "68") (name "unconnected-(U1-PB6-Pad45)") (class "Default")
      (node (ref "U1") (pin "45") (pinfunction "PB6_45") (pintype "bidirectional"))
    )
    (net (code "69") (name "unconnected-(U1-PB7-Pad46)") (class "Default")
      (node (ref "U1") (pin "46") (pinfunction "PB7_46") (pintype "bidirectional"))
    )
    (net (code "70") (name "unconnected-(U1-PB10-Pad22)") (class "Default")
      (node (ref "U1") (pin "22") (pinfunction "PB10_22") (pintype "bidirectional"))
    )
    (net (code "71") (name "unconnected-(U1-PB15-Pad27)") (class "Default")
      (node (ref "U1") (pin "27") (pinfunction "PB15_27") (pintype "bidirectional"))
    )
    (net (code "72") (name "unconnected-(U1-PC14-OSC32_IN-Pad2)") (class "Default")
      (node (ref "U1") (pin "2") (pinfunction "PC14-OSC32_IN_2") (pintype "bidirectional"))
    )
    (net (code "73") (name "unconnected-(U1-PC15-OSC32_OUT-Pad3)") (class "Default")
      (node (ref "U1") (pin "3") (pinfunction "PC15-OSC32_OUT_3") (pintype "bidirectional"))
    )
    (net (code "74") (name "unconnected-(U1-PD1-Pad39)") (class "Default")
      (node (ref "U1") (pin "39") (pinfunction "PD1_39") (pintype "bidirectional"))
    )
  )
)
